# Amplifier.net
KiCad netlist of a schematic drawn in EAGLE
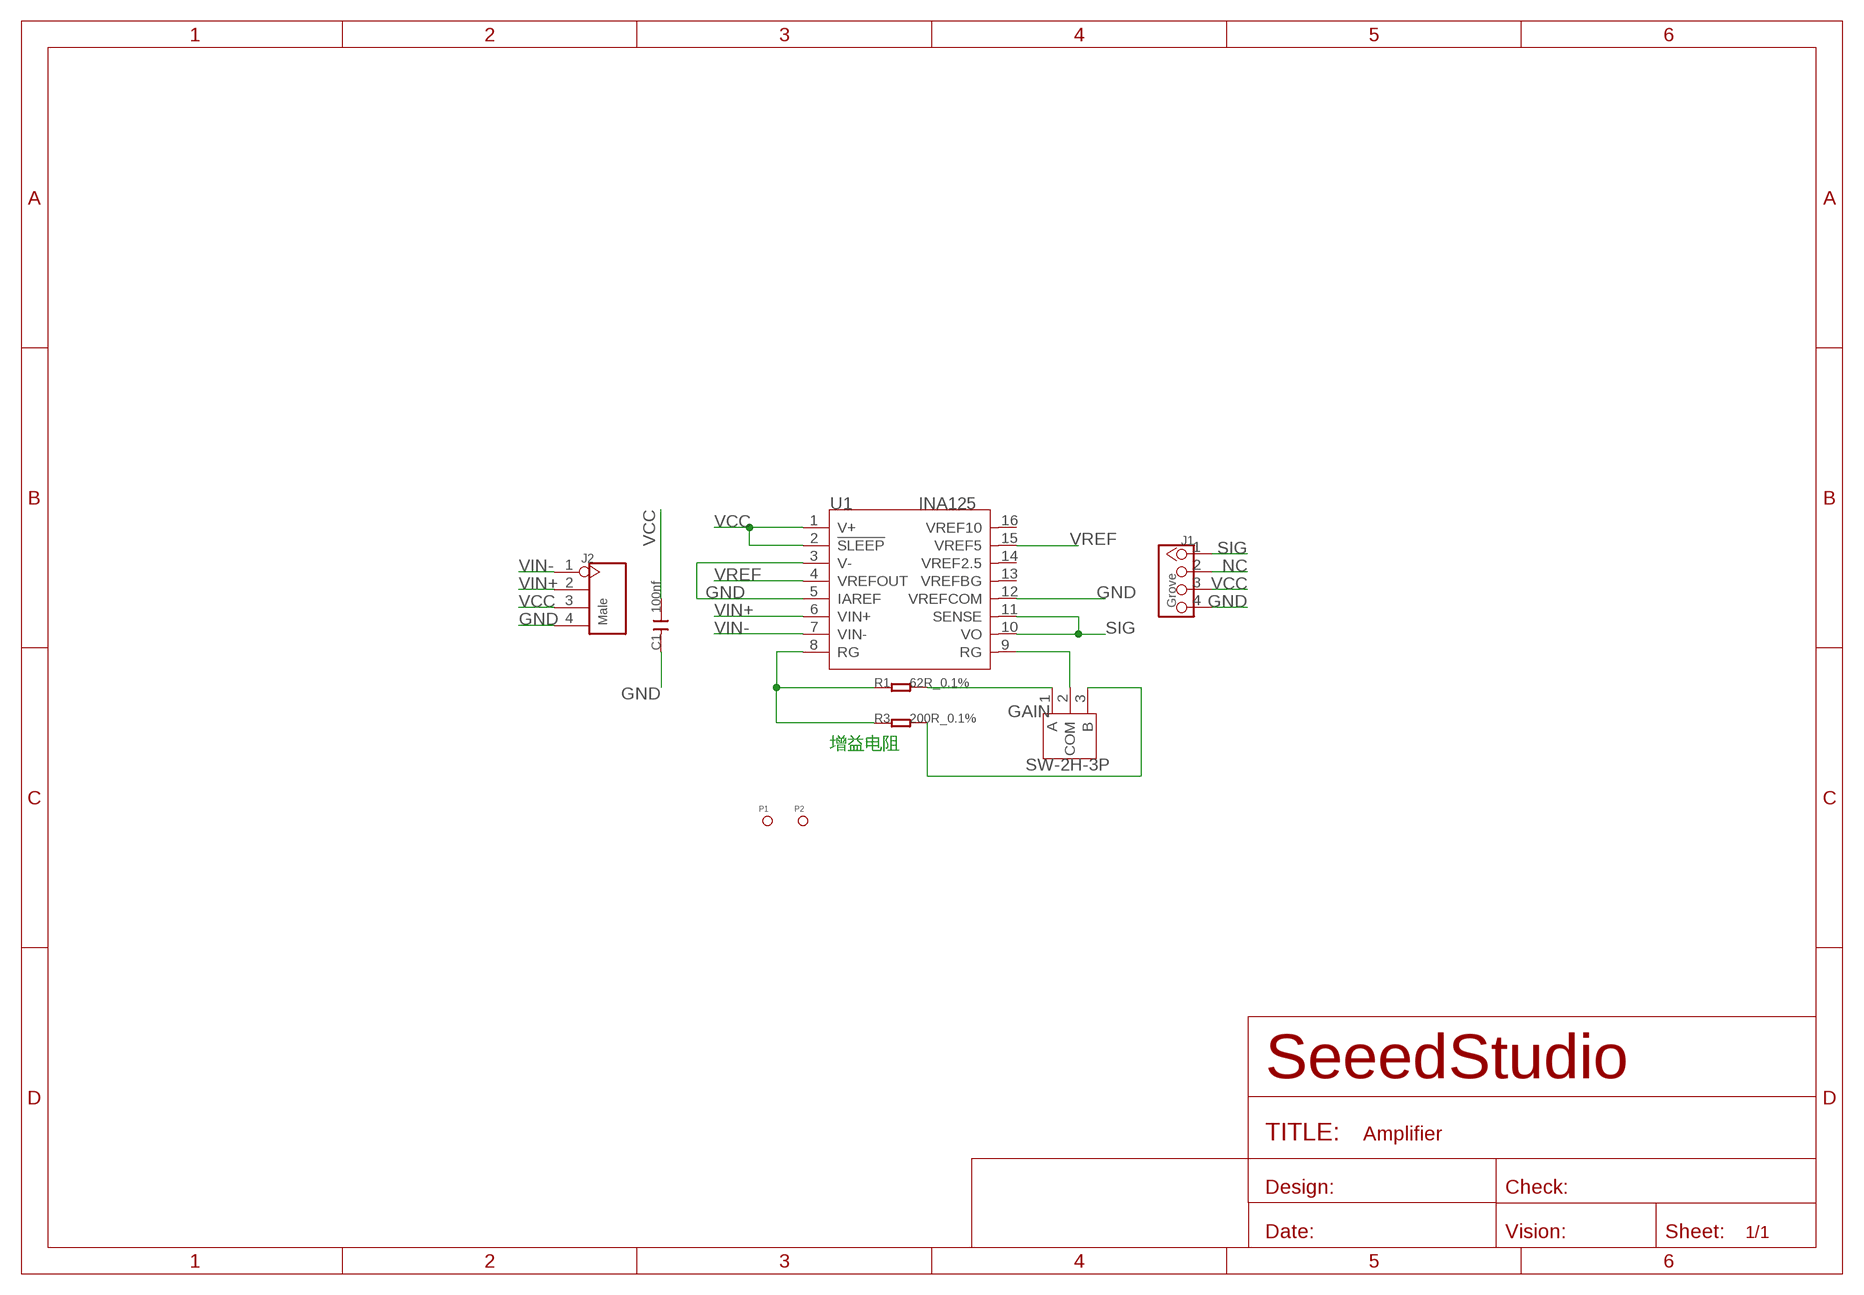
[diagram p0: schematic, sheet 1]

(export (version "E")
  (design (tool "Eeschema 10.0.6"))
  (components
    (comp (ref "C1")
      (value "100nf")
      (footprint "eagle-import:C0805")
      (libsource (lib "eagle-import") (part "C-0805"))
    )
    (comp (ref "GAIN")
      (value "SW-2H-3P")
      (footprint "eagle-import:3P-2CH-3.54X8.5")
      (libsource (lib "eagle-import") (part "SWITCH-2H-3P'--'"))
    )
    (comp (ref "J1")
      (value "Grove")
      (footprint "eagle-import:4P-2.0")
      (libsource (lib "eagle-import") (part "TWIG-4P-2.0-2.0"))
    )
    (comp (ref "J2")
      (value "Male")
      (footprint "eagle-import:4P-65_35MIL")
      (libsource (lib "eagle-import") (part "HEADER-4P-60/35MIL"))
    )
    (comp (ref "P1")
      (value "PAD-MARK")
      (footprint "eagle-import:ROUND-MARK-1.0")
      (fields (field (name "PARTNO") "DNP"))
      (libsource (lib "eagle-import") (part "PAD-MARK"))
    )
    (comp (ref "P2")
      (value "PAD-MARK")
      (footprint "eagle-import:ROUND-MARK-1.0")
      (fields (field (name "PARTNO") "DNP"))
      (libsource (lib "eagle-import") (part "PAD-MARK"))
    )
    (comp (ref "R1")
      (value "62R_0.1%")
      (footprint "eagle-import:R0805")
      (libsource (lib "eagle-import") (part "R-0805"))
    )
    (comp (ref "R3")
      (value "200R_0.1%")
      (footprint "eagle-import:R0805")
      (libsource (lib "eagle-import") (part "R-0805"))
    )
    (comp (ref "U1")
      (value "INA125")
      (footprint "eagle-import:SO16")
      (libsource (lib "eagle-import") (part "INA125U"))
    )
  )
  (nets
    (net (code "1") (name "/GND") (class "Default")
      (node (ref "C1") (pin "2") (pinfunction "2_2") (pintype "passive"))
      (node (ref "J1") (pin "4") (pinfunction "4_4") (pintype "bidirectional"))
      (node (ref "J2") (pin "4") (pinfunction "P$4_4") (pintype "bidirectional"))
      (node (ref "U1") (pin "12") (pinfunction "VREFCOM_12") (pintype "bidirectional"))
      (node (ref "U1") (pin "3") (pinfunction "V-_3") (pintype "bidirectional"))
      (node (ref "U1") (pin "5") (pinfunction "IAREF_5") (pintype "bidirectional"))
    )
    (net (code "2") (name "/NC") (class "Default")
      (node (ref "J1") (pin "2") (pinfunction "2_2") (pintype "bidirectional"))
    )
    (net (code "3") (name "/SIG") (class "Default")
      (node (ref "J1") (pin "1") (pinfunction "1_1") (pintype "bidirectional"))
      (node (ref "U1") (pin "10") (pinfunction "VO_10") (pintype "bidirectional"))
      (node (ref "U1") (pin "11") (pinfunction "SENSE_11") (pintype "bidirectional"))
    )
    (net (code "4") (name "/VCC") (class "Default")
      (node (ref "C1") (pin "1") (pinfunction "1_1") (pintype "passive"))
      (node (ref "J1") (pin "3") (pinfunction "3_3") (pintype "bidirectional"))
      (node (ref "J2") (pin "3") (pinfunction "P$3_3") (pintype "bidirectional"))
      (node (ref "U1") (pin "1") (pinfunction "V+_1") (pintype "bidirectional"))
      (node (ref "U1") (pin "2") (pinfunction "~{SLEEP}_2") (pintype "bidirectional"))
    )
    (net (code "5") (name "/VIN+") (class "Default")
      (node (ref "J2") (pin "2") (pinfunction "P$2_2") (pintype "bidirectional"))
      (node (ref "U1") (pin "6") (pinfunction "VIN+_6") (pintype "bidirectional"))
    )
    (net (code "6") (name "/VIN-") (class "Default")
      (node (ref "J2") (pin "1") (pinfunction "P$1_1") (pintype "bidirectional"))
      (node (ref "U1") (pin "7") (pinfunction "VIN-_7") (pintype "bidirectional"))
    )
    (net (code "7") (name "/VREF") (class "Default")
      (node (ref "U1") (pin "15") (pinfunction "VREF5_15") (pintype "bidirectional"))
      (node (ref "U1") (pin "4") (pinfunction "VREFOUT_4") (pintype "bidirectional"))
    )
    (net (code "8") (name "Net-(GAIN-A)") (class "Default")
      (node (ref "GAIN") (pin "1") (pinfunction "A_1") (pintype "bidirectional"))
      (node (ref "R1") (pin "2") (pinfunction "2_2") (pintype "passive"))
    )
    (net (code "9") (name "Net-(GAIN-B)") (class "Default")
      (node (ref "GAIN") (pin "3") (pinfunction "B_3") (pintype "bidirectional"))
      (node (ref "R3") (pin "2") (pinfunction "2_2") (pintype "passive"))
    )
    (net (code "10") (name "Net-(GAIN-COM)") (class "Default")
      (node (ref "GAIN") (pin "2") (pinfunction "COM_2") (pintype "bidirectional"))
      (node (ref "U1") (pin "9") (pinfunction "RG_9") (pintype "bidirectional"))
    )
    (net (code "11") (name "Net-(R1-Pad1)") (class "Default")
      (node (ref "R1") (pin "1") (pinfunction "1_1") (pintype "passive"))
      (node (ref "R3") (pin "1") (pinfunction "1_1") (pintype "passive"))
      (node (ref "U1") (pin "8") (pinfunction "RG_8") (pintype "bidirectional"))
    )
    (net (code "12") (name "unconnected-(U1-VREF2.5-Pad14)") (class "Default")
      (node (ref "U1") (pin "14") (pinfunction "VREF2.5_14") (pintype "bidirectional"))
    )
    (net (code "13") (name "unconnected-(U1-VREF10-Pad16)") (class "Default")
      (node (ref "U1") (pin "16") (pinfunction "VREF10_16") (pintype "bidirectional"))
    )
    (net (code "14") (name "unconnected-(U1-VREFBG-Pad13)") (class "Default")
      (node (ref "U1") (pin "13") (pinfunction "VREFBG_13") (pintype "bidirectional"))
    )
  )
)
